# Board5.net
KiCad netlist of a schematic drawn in EAGLE
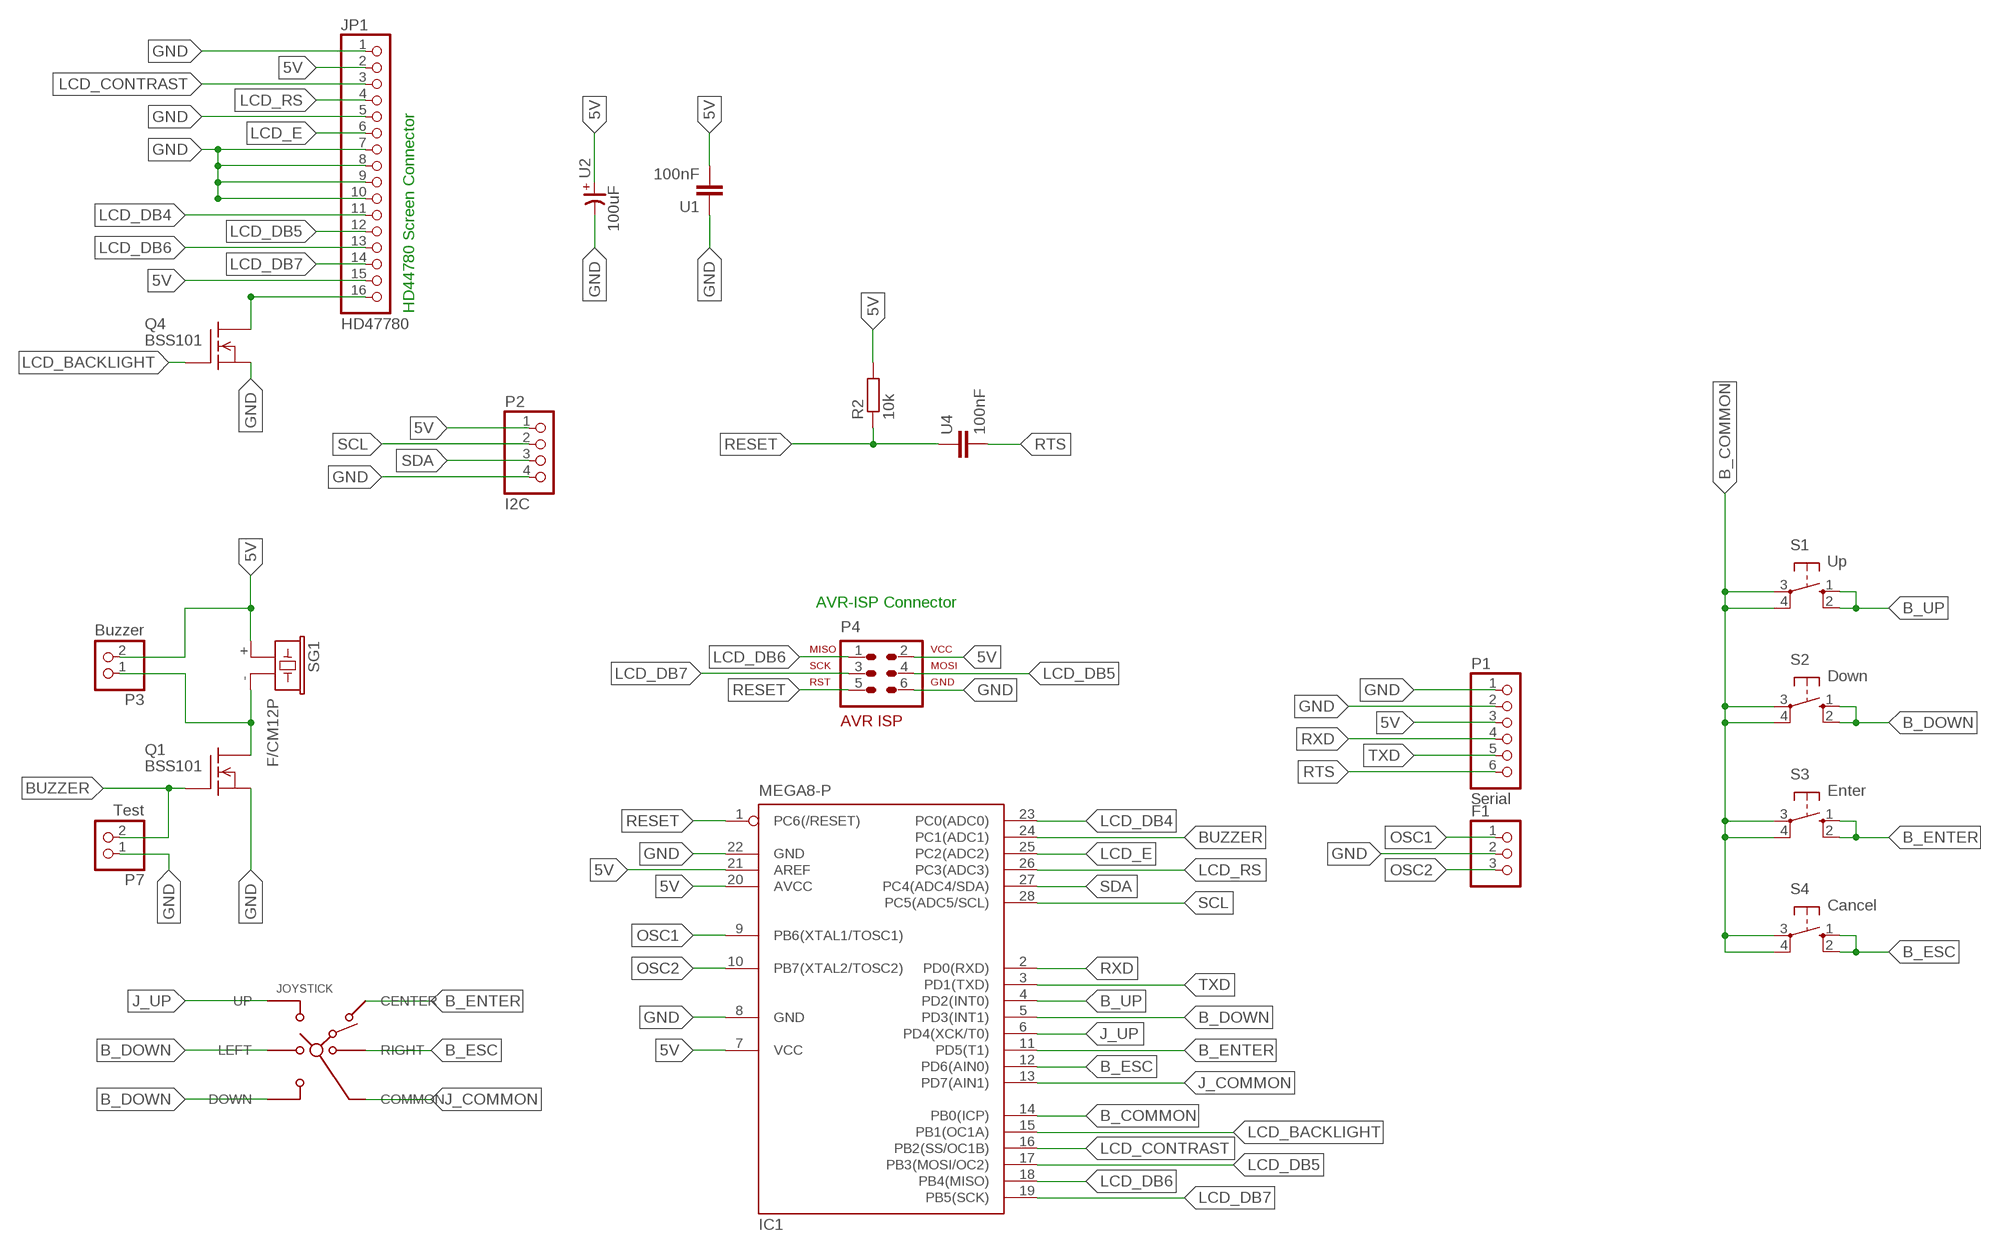
[diagram p0: schematic, sheet 1]

(export (version "E")
  (design (tool "Eeschema 10.0.6"))
  (components
    (comp (ref "F1")
      (value "PINHD-1X3")
      (footprint "eagle-import:1X03")
      (libsource (lib "eagle-import") (part "PINHD-1X3"))
    )
    (comp (ref "IC1")
      (value "MEGA8-P")
      (footprint "eagle-import:DIL28-3")
      (libsource (lib "eagle-import") (part "MEGA8-P"))
    )
    (comp (ref "JOYSTICK")
      (value "SKQUAAA010")
      (footprint "eagle-import:SKQU")
      (fields (field (name "MF") "ALPS"))
      (libsource (lib "eagle-import") (part "SKQUAAA010"))
    )
    (comp (ref "JP1")
      (value "HD47780")
      (footprint "eagle-import:1X16")
      (libsource (lib "eagle-import") (part "PINHD-1X16"))
    )
    (comp (ref "P1")
      (value "Serial")
      (footprint "eagle-import:1X06")
      (libsource (lib "eagle-import") (part "PINHD-1X6"))
    )
    (comp (ref "P2")
      (value "I2C")
      (footprint "eagle-import:1X04")
      (libsource (lib "eagle-import") (part "PINHD-1X4"))
    )
    (comp (ref "P3")
      (value "Buzzer")
      (footprint "eagle-import:1X02")
      (libsource (lib "eagle-import") (part "PINHD-1X2"))
    )
    (comp (ref "P4")
      (value "ISP_WANNENBUCHSE")
      (footprint "eagle-import:ML6")
      (libsource (lib "eagle-import") (part "ISP_WANNENBUCHSE"))
    )
    (comp (ref "P7")
      (value "Test")
      (footprint "eagle-import:1X02")
      (libsource (lib "eagle-import") (part "PINHD-1X2"))
    )
    (comp (ref "Q1")
      (value "BSS101")
      (footprint "eagle-import:TO92")
      (libsource (lib "eagle-import") (part "BSS101"))
    )
    (comp (ref "Q4")
      (value "BSS101")
      (footprint "eagle-import:TO92")
      (libsource (lib "eagle-import") (part "BSS101"))
    )
    (comp (ref "R2")
      (value "10k")
      (footprint "eagle-import:0207_10")
      (libsource (lib "eagle-import") (part "R-EU_0207/10"))
    )
    (comp (ref "S1")
      (value "Up")
      (footprint "eagle-import:B3F-40XX")
      (libsource (lib "eagle-import") (part "40-XX"))
    )
    (comp (ref "S2")
      (value "Down")
      (footprint "eagle-import:B3F-40XX")
      (libsource (lib "eagle-import") (part "40-XX"))
    )
    (comp (ref "S3")
      (value "Enter")
      (footprint "eagle-import:B3F-40XX")
      (libsource (lib "eagle-import") (part "40-XX"))
    )
    (comp (ref "S4")
      (value "Cancel")
      (footprint "eagle-import:B3F-40XX")
      (libsource (lib "eagle-import") (part "40-XX"))
    )
    (comp (ref "SG1")
      (value "F/CM12P")
      (footprint "eagle-import:F_CM12P")
      (libsource (lib "eagle-import") (part "F/CM12P"))
    )
    (comp (ref "U1")
      (value "100nF")
      (footprint "eagle-import:C050-024X044")
      (libsource (lib "eagle-import") (part "C-EU050-024X044"))
    )
    (comp (ref "U2")
      (value "100uF")
      (footprint "eagle-import:E-020X050")
      (libsource (lib "eagle-import") (part "CP-E-020X050"))
    )
    (comp (ref "U4")
      (value "100nF")
      (footprint "eagle-import:C050-024X044")
      (libsource (lib "eagle-import") (part "C-EU050-024X044"))
    )
  )
  (nets
    (net (code "1") (name "5V") (class "Default")
      (node (ref "IC1") (pin "20") (pinfunction "AVCC_20") (pintype "power_in"))
      (node (ref "IC1") (pin "21") (pinfunction "AREF_21") (pintype "passive"))
      (node (ref "IC1") (pin "7") (pinfunction "VCC_7") (pintype "power_in"))
      (node (ref "JP1") (pin "15") (pinfunction "15_15") (pintype "passive"))
      (node (ref "JP1") (pin "2") (pinfunction "2_2") (pintype "passive"))
      (node (ref "P1") (pin "3") (pinfunction "3_3") (pintype "passive"))
      (node (ref "P2") (pin "1") (pinfunction "1_1") (pintype "passive"))
      (node (ref "P3") (pin "2") (pinfunction "2_2") (pintype "passive"))
      (node (ref "P4") (pin "2") (pinfunction "VCC_2") (pintype "passive"))
      (node (ref "R2") (pin "2") (pinfunction "2_2") (pintype "passive"))
      (node (ref "SG1") (pin "+") (pinfunction "1_+") (pintype "passive"))
      (node (ref "U1") (pin "2") (pinfunction "2_2") (pintype "passive"))
      (node (ref "U2") (pin "+") (pinfunction "+_+") (pintype "passive"))
    )
    (net (code "2") (name "BUZZER") (class "Default")
      (node (ref "IC1") (pin "24") (pinfunction "PC1(ADC1)_24") (pintype "bidirectional"))
      (node (ref "P7") (pin "2") (pinfunction "2_2") (pintype "passive"))
      (node (ref "Q1") (pin "2") (pinfunction "G_2") (pintype "passive"))
    )
    (net (code "3") (name "B_COMMON") (class "Default")
      (node (ref "IC1") (pin "14") (pinfunction "PB0(ICP)_14") (pintype "bidirectional"))
      (node (ref "S1") (pin "3") (pinfunction "P_3") (pintype "passive"))
      (node (ref "S1") (pin "4") (pinfunction "P1_4") (pintype "passive"))
      (node (ref "S2") (pin "3") (pinfunction "P_3") (pintype "passive"))
      (node (ref "S2") (pin "4") (pinfunction "P1_4") (pintype "passive"))
      (node (ref "S3") (pin "3") (pinfunction "P_3") (pintype "passive"))
      (node (ref "S3") (pin "4") (pinfunction "P1_4") (pintype "passive"))
      (node (ref "S4") (pin "3") (pinfunction "P_3") (pintype "passive"))
      (node (ref "S4") (pin "4") (pinfunction "P1_4") (pintype "passive"))
    )
    (net (code "4") (name "B_DOWN") (class "Default")
      (node (ref "IC1") (pin "5") (pinfunction "PD3(INT1)_5") (pintype "bidirectional"))
      (node (ref "JOYSTICK") (pin "DOWN") (pinfunction "DOWN_DOWN") (pintype "passive"))
      (node (ref "JOYSTICK") (pin "LEFT") (pinfunction "LEFT_LEFT") (pintype "passive"))
      (node (ref "S2") (pin "1") (pinfunction "S_1") (pintype "passive"))
      (node (ref "S2") (pin "2") (pinfunction "S1_2") (pintype "passive"))
    )
    (net (code "5") (name "B_ENTER") (class "Default")
      (node (ref "IC1") (pin "11") (pinfunction "PD5(T1)_11") (pintype "bidirectional"))
      (node (ref "JOYSTICK") (pin "CENTER") (pinfunction "CENTER_CENTER") (pintype "passive"))
      (node (ref "S3") (pin "1") (pinfunction "S_1") (pintype "passive"))
      (node (ref "S3") (pin "2") (pinfunction "S1_2") (pintype "passive"))
    )
    (net (code "6") (name "B_ESC") (class "Default")
      (node (ref "IC1") (pin "12") (pinfunction "PD6(AIN0)_12") (pintype "bidirectional"))
      (node (ref "JOYSTICK") (pin "RIGHT") (pinfunction "RIGHT_RIGHT") (pintype "passive"))
      (node (ref "S4") (pin "1") (pinfunction "S_1") (pintype "passive"))
      (node (ref "S4") (pin "2") (pinfunction "S1_2") (pintype "passive"))
    )
    (net (code "7") (name "B_UP") (class "Default")
      (node (ref "IC1") (pin "4") (pinfunction "PD2(INT0)_4") (pintype "bidirectional"))
      (node (ref "S1") (pin "1") (pinfunction "S_1") (pintype "passive"))
      (node (ref "S1") (pin "2") (pinfunction "S1_2") (pintype "passive"))
    )
    (net (code "8") (name "GND") (class "Default")
      (node (ref "F1") (pin "2") (pinfunction "2_2") (pintype "passive"))
      (node (ref "IC1") (pin "22") (pinfunction "GND_22") (pintype "power_in"))
      (node (ref "IC1") (pin "8") (pinfunction "GND_8") (pintype "power_in"))
      (node (ref "JP1") (pin "1") (pinfunction "1_1") (pintype "passive"))
      (node (ref "JP1") (pin "10") (pinfunction "10_10") (pintype "passive"))
      (node (ref "JP1") (pin "5") (pinfunction "5_5") (pintype "passive"))
      (node (ref "JP1") (pin "7") (pinfunction "7_7") (pintype "passive"))
      (node (ref "JP1") (pin "8") (pinfunction "8_8") (pintype "passive"))
      (node (ref "JP1") (pin "9") (pinfunction "9_9") (pintype "passive"))
      (node (ref "P1") (pin "1") (pinfunction "1_1") (pintype "passive"))
      (node (ref "P1") (pin "2") (pinfunction "2_2") (pintype "passive"))
      (node (ref "P2") (pin "4") (pinfunction "4_4") (pintype "passive"))
      (node (ref "P4") (pin "6") (pinfunction "GND_6") (pintype "passive"))
      (node (ref "P7") (pin "1") (pinfunction "1_1") (pintype "passive"))
      (node (ref "Q1") (pin "1") (pinfunction "S_1") (pintype "passive"))
      (node (ref "Q4") (pin "1") (pinfunction "S_1") (pintype "passive"))
      (node (ref "U1") (pin "1") (pinfunction "1_1") (pintype "passive"))
      (node (ref "U2") (pin "-") (pinfunction "-_-") (pintype "passive"))
    )
    (net (code "9") (name "J_COMMON") (class "Default")
      (node (ref "IC1") (pin "13") (pinfunction "PD7(AIN1)_13") (pintype "bidirectional"))
      (node (ref "JOYSTICK") (pin "COMMON") (pinfunction "COMMON_COMMON") (pintype "power_in"))
    )
    (net (code "10") (name "J_UP") (class "Default")
      (node (ref "IC1") (pin "6") (pinfunction "PD4(XCK/T0)_6") (pintype "bidirectional"))
      (node (ref "JOYSTICK") (pin "UP") (pinfunction "UP_UP") (pintype "passive"))
    )
    (net (code "11") (name "LCD_BACKLIGHT") (class "Default")
      (node (ref "IC1") (pin "15") (pinfunction "PB1(OC1A)_15") (pintype "bidirectional"))
      (node (ref "Q4") (pin "2") (pinfunction "G_2") (pintype "passive"))
    )
    (net (code "12") (name "LCD_CONTRAST") (class "Default")
      (node (ref "IC1") (pin "16") (pinfunction "PB2(SS/OC1B)_16") (pintype "bidirectional"))
      (node (ref "JP1") (pin "3") (pinfunction "3_3") (pintype "passive"))
    )
    (net (code "13") (name "LCD_DB4") (class "Default")
      (node (ref "IC1") (pin "23") (pinfunction "PC0(ADC0)_23") (pintype "bidirectional"))
      (node (ref "JP1") (pin "11") (pinfunction "11_11") (pintype "passive"))
    )
    (net (code "14") (name "LCD_DB5") (class "Default")
      (node (ref "IC1") (pin "17") (pinfunction "PB3(MOSI/OC2)_17") (pintype "bidirectional"))
      (node (ref "JP1") (pin "12") (pinfunction "12_12") (pintype "passive"))
      (node (ref "P4") (pin "4") (pinfunction "MOSI_4") (pintype "passive"))
    )
    (net (code "15") (name "LCD_DB6") (class "Default")
      (node (ref "IC1") (pin "18") (pinfunction "PB4(MISO)_18") (pintype "bidirectional"))
      (node (ref "JP1") (pin "13") (pinfunction "13_13") (pintype "passive"))
      (node (ref "P4") (pin "1") (pinfunction "MISO_1") (pintype "passive"))
    )
    (net (code "16") (name "LCD_DB7") (class "Default")
      (node (ref "IC1") (pin "19") (pinfunction "PB5(SCK)_19") (pintype "bidirectional"))
      (node (ref "JP1") (pin "14") (pinfunction "14_14") (pintype "passive"))
      (node (ref "P4") (pin "3") (pinfunction "SCK_3") (pintype "passive"))
    )
    (net (code "17") (name "LCD_E") (class "Default")
      (node (ref "IC1") (pin "25") (pinfunction "PC2(ADC2)_25") (pintype "bidirectional"))
      (node (ref "JP1") (pin "6") (pinfunction "6_6") (pintype "passive"))
    )
    (net (code "18") (name "LCD_RS") (class "Default")
      (node (ref "IC1") (pin "26") (pinfunction "PC3(ADC3)_26") (pintype "bidirectional"))
      (node (ref "JP1") (pin "4") (pinfunction "4_4") (pintype "passive"))
    )
    (net (code "19") (name "Net-(Q1-D)") (class "Default")
      (node (ref "P3") (pin "1") (pinfunction "1_1") (pintype "passive"))
      (node (ref "Q1") (pin "3") (pinfunction "D_3") (pintype "passive"))
      (node (ref "SG1") (pin "-") (pinfunction "2_-") (pintype "passive"))
    )
    (net (code "20") (name "Net-(Q4-D)") (class "Default")
      (node (ref "JP1") (pin "16") (pinfunction "16_16") (pintype "passive"))
      (node (ref "Q4") (pin "3") (pinfunction "D_3") (pintype "passive"))
    )
    (net (code "21") (name "OSC1") (class "Default")
      (node (ref "F1") (pin "1") (pinfunction "1_1") (pintype "passive"))
      (node (ref "IC1") (pin "9") (pinfunction "PB6(XTAL1/TOSC1)_9") (pintype "bidirectional"))
    )
    (net (code "22") (name "OSC2") (class "Default")
      (node (ref "F1") (pin "3") (pinfunction "3_3") (pintype "passive"))
      (node (ref "IC1") (pin "10") (pinfunction "PB7(XTAL2/TOSC2)_10") (pintype "bidirectional"))
    )
    (net (code "23") (name "RESET") (class "Default")
      (node (ref "IC1") (pin "1") (pinfunction "PC6(/RESET)_1") (pintype "bidirectional"))
      (node (ref "P4") (pin "5") (pinfunction "RST_5") (pintype "passive"))
      (node (ref "R2") (pin "1") (pinfunction "1_1") (pintype "passive"))
      (node (ref "U4") (pin "1") (pinfunction "1_1") (pintype "passive"))
    )
    (net (code "24") (name "RTS") (class "Default")
      (node (ref "P1") (pin "6") (pinfunction "6_6") (pintype "passive"))
      (node (ref "U4") (pin "2") (pinfunction "2_2") (pintype "passive"))
    )
    (net (code "25") (name "RXD") (class "Default")
      (node (ref "IC1") (pin "2") (pinfunction "PD0(RXD)_2") (pintype "bidirectional"))
      (node (ref "P1") (pin "4") (pinfunction "4_4") (pintype "passive"))
    )
    (net (code "26") (name "SCL") (class "Default")
      (node (ref "IC1") (pin "28") (pinfunction "PC5(ADC5/SCL)_28") (pintype "bidirectional"))
      (node (ref "P2") (pin "2") (pinfunction "2_2") (pintype "passive"))
    )
    (net (code "27") (name "SDA") (class "Default")
      (node (ref "IC1") (pin "27") (pinfunction "PC4(ADC4/SDA)_27") (pintype "bidirectional"))
      (node (ref "P2") (pin "3") (pinfunction "3_3") (pintype "passive"))
    )
    (net (code "28") (name "TXD") (class "Default")
      (node (ref "IC1") (pin "3") (pinfunction "PD1(TXD)_3") (pintype "bidirectional"))
      (node (ref "P1") (pin "5") (pinfunction "5_5") (pintype "passive"))
    )
  )
)
